# CheeseCake_1StAnn_SP.net
KiCad netlist of a schematic drawn in EasyEDA Pro
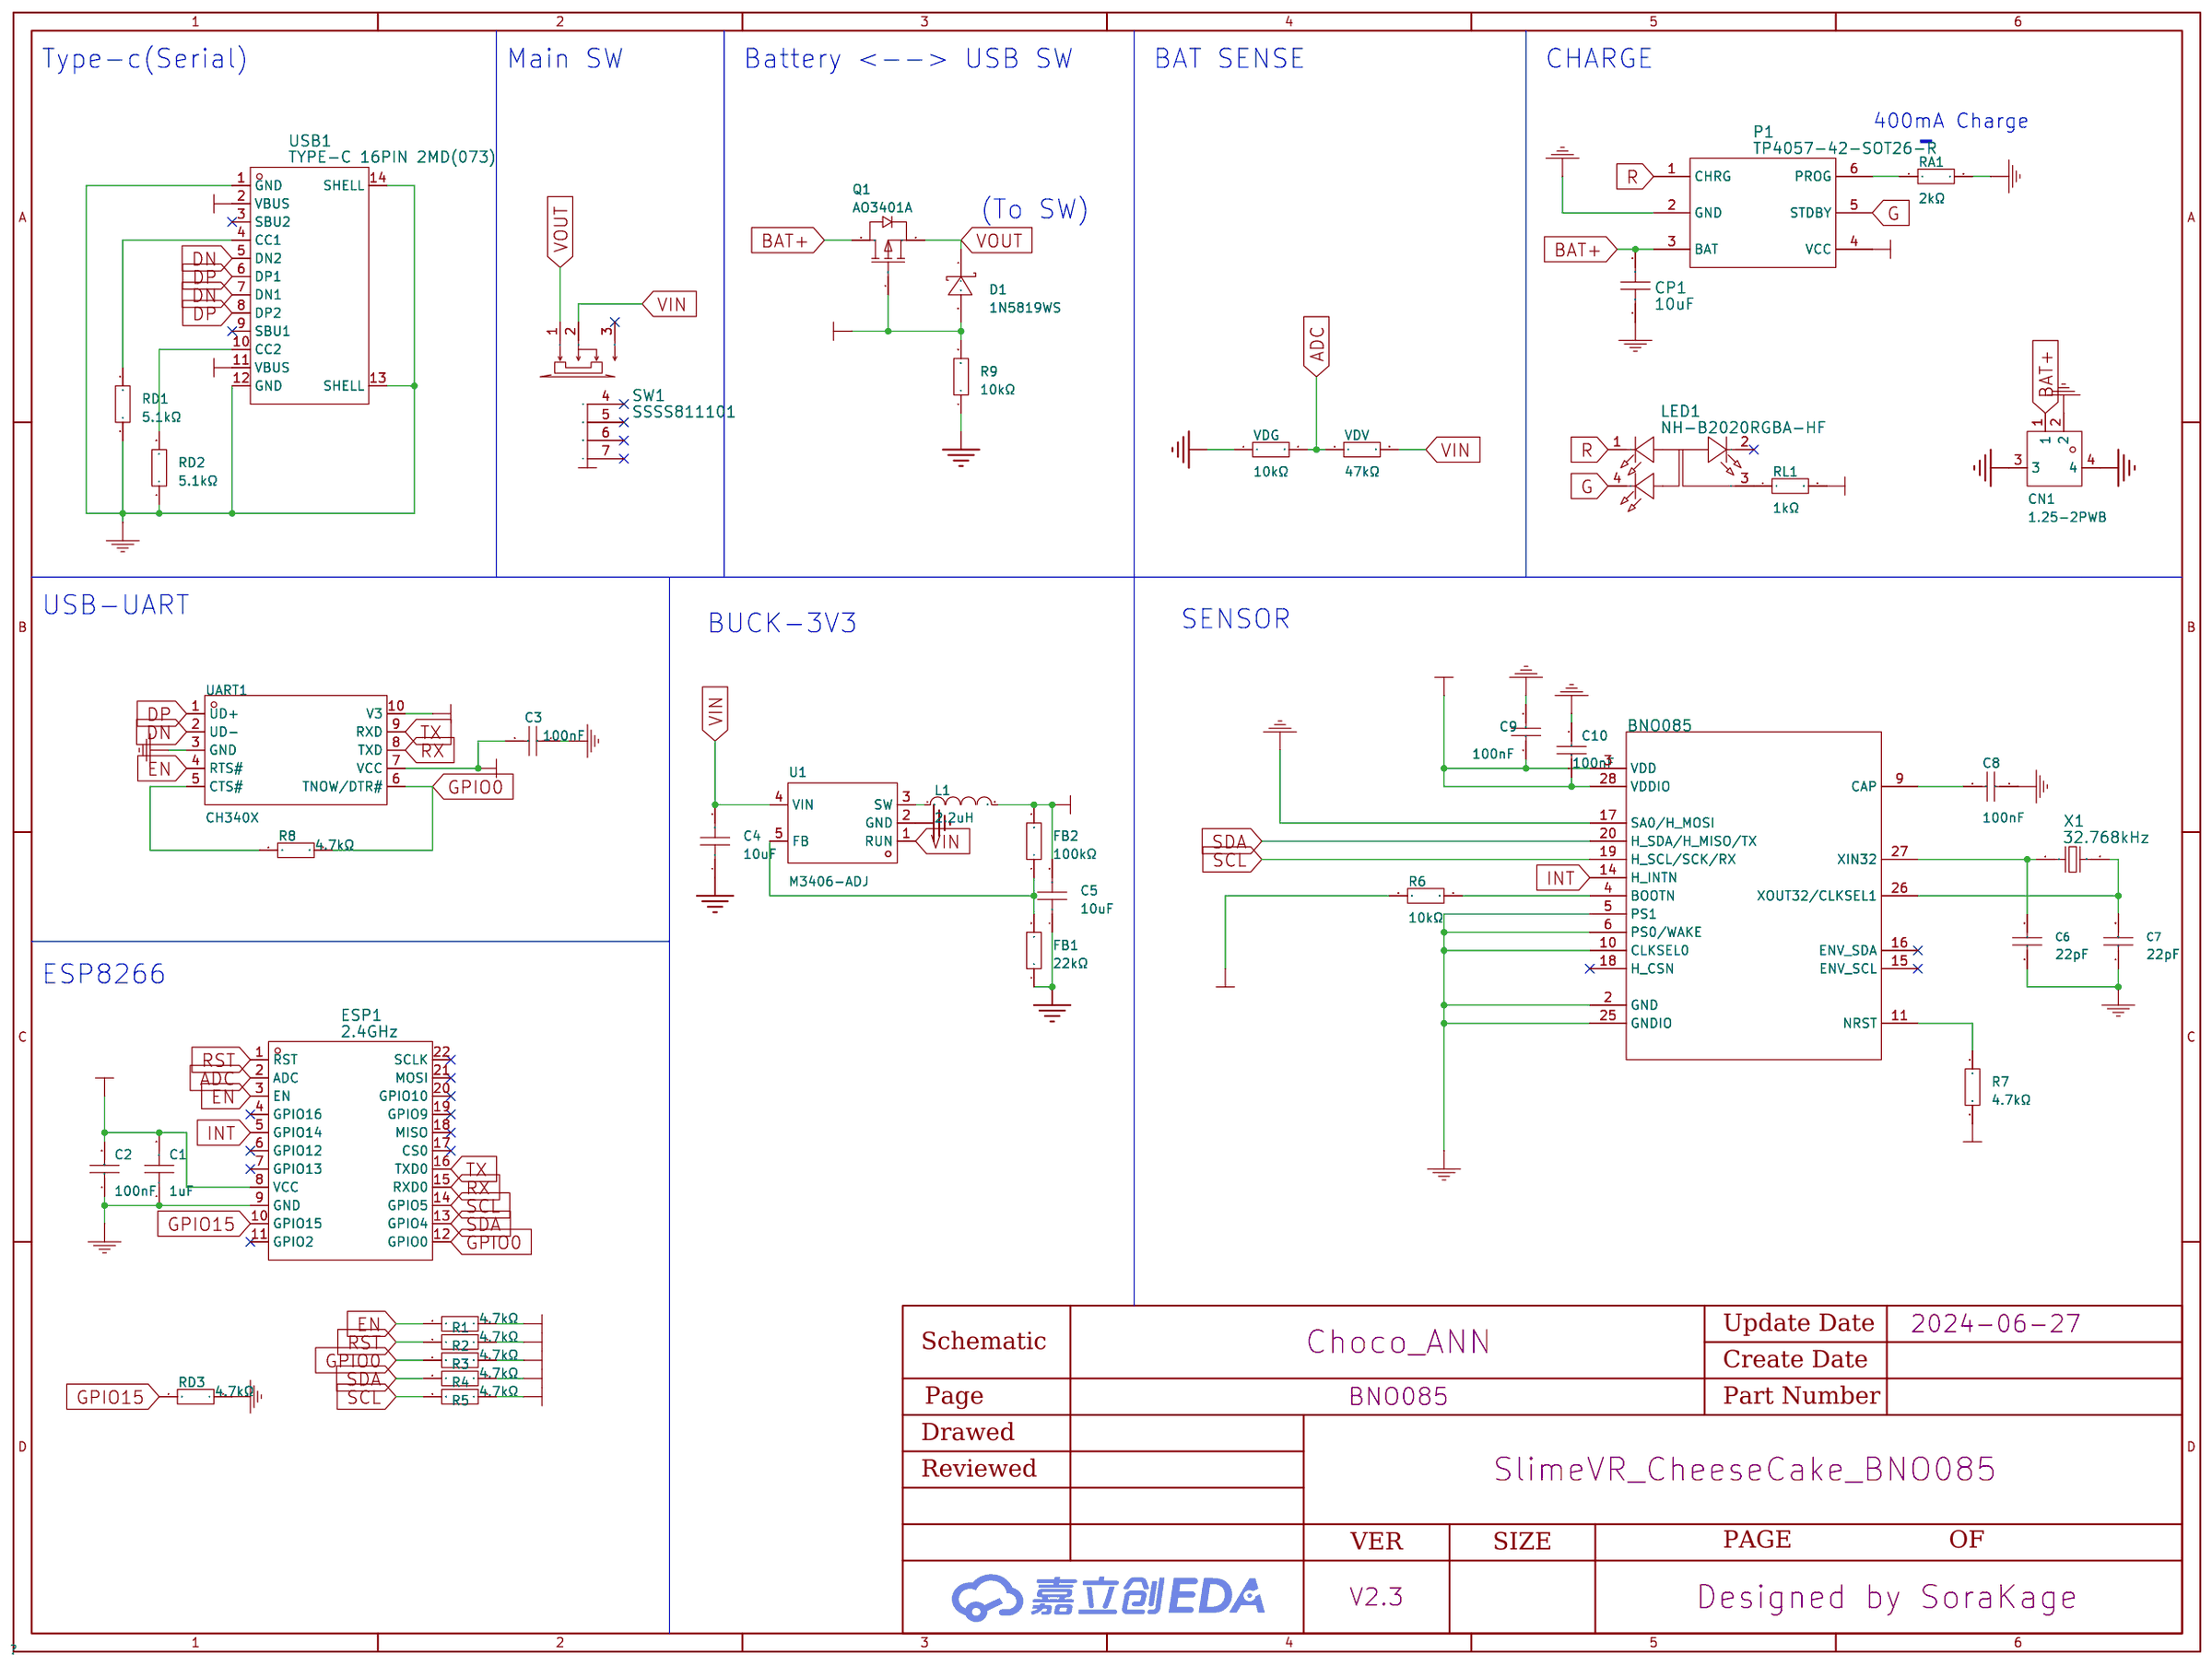
[diagram p0: schematic sheet]

(export (version "E")
  (design (tool "Eeschema 10.0.6"))
  (components
    (comp (ref "BNO085")
      (value "BNO080")
      (fields (field (name "Manufacturer Part") "BNO085") (field (name "Manufacturer") "Hillcrest"))
      (libsource (lib "easyedapro") (part "BNO080"))
    )
    (comp (ref "C1")
      (value "1uF")
      (footprint "easyedapro:C0402")
      (description "容值:1uF;精度:±10%;额定电压:25V;材质(温度系数):X5R;")
      (fields
        (field (name "Manufacturer Part") "CL05A105KA5NQNC")
        (field (name "Manufacturer") "SAMSUNG(三星)")
      )
      (libsource (lib "easyedapro") (part "CL05A105KA5NQNC"))
    )
    (comp (ref "C2")
      (value "100nF")
      (footprint "easyedapro:C0402")
      (description "容值:100nF;精度:±10%;额定电压:16V;材质(温度系数):X7R;")
      (fields
        (field (name "Manufacturer Part") "CL05B104KO5NNNC")
        (field (name "Manufacturer") "SAMSUNG(三星)")
      )
      (libsource (lib "easyedapro") (part "CL05B104KO5NNNC"))
    )
    (comp (ref "C3")
      (value "100nF")
      (footprint "easyedapro:C0402")
      (description "容值:100nF;精度:±10%;额定电压:16V;材质(温度系数):X7R;")
      (fields
        (field (name "Manufacturer Part") "CL05B104KO5NNNC")
        (field (name "Manufacturer") "SAMSUNG(三星)")
      )
      (libsource (lib "easyedapro") (part "CL05B104KO5NNNC"))
    )
    (comp (ref "C4")
      (value "10uF")
      (footprint "easyedapro:C0603")
      (description "容值:10uF;精度:±10%;额定电压:10V;材质(温度系数):X5R;")
      (fields
        (field (name "Manufacturer Part") "CL10A106KP8NNNC")
        (field (name "Manufacturer") "SAMSUNG(三星)")
      )
      (libsource (lib "easyedapro") (part "CL10A106KP8NNNC"))
    )
    (comp (ref "C5")
      (value "10uF")
      (footprint "easyedapro:C0603")
      (description "容值:10uF;精度:±10%;额定电压:10V;材质(温度系数):X5R;")
      (fields
        (field (name "Manufacturer Part") "CL10A106KP8NNNC")
        (field (name "Manufacturer") "SAMSUNG(三星)")
      )
      (libsource (lib "easyedapro") (part "CL10A106KP8NNNC"))
    )
    (comp (ref "C6")
      (value "22pF")
      (footprint "easyedapro:C0402")
      (description "容值:22pF;精度:±5%;额定电压:50V;材质(温度系数):C0G;")
      (fields (field (name "Manufacturer Part") "0402CG220J500NT") (field (name "Manufacturer") "FH(风华)"))
      (libsource (lib "easyedapro") (part "0402CG220J500NT"))
    )
    (comp (ref "C7")
      (value "22pF")
      (footprint "easyedapro:C0402")
      (description "容值:22pF;精度:±5%;额定电压:50V;材质(温度系数):C0G;")
      (fields (field (name "Manufacturer Part") "0402CG220J500NT") (field (name "Manufacturer") "FH(风华)"))
      (libsource (lib "easyedapro") (part "0402CG220J500NT"))
    )
    (comp (ref "C8")
      (value "100nF")
      (footprint "easyedapro:C0402")
      (description "容值:100nF;精度:±10%;额定电压:16V;材质(温度系数):X7R;")
      (fields
        (field (name "Manufacturer Part") "CL05B104KO5NNNC")
        (field (name "Manufacturer") "SAMSUNG(三星)")
      )
      (libsource (lib "easyedapro") (part "CL05B104KO5NNNC"))
    )
    (comp (ref "C9")
      (value "100nF")
      (footprint "easyedapro:C0402")
      (description "容值:100nF;精度:±10%;额定电压:16V;材质(温度系数):X7R;")
      (fields
        (field (name "Manufacturer Part") "CL05B104KO5NNNC")
        (field (name "Manufacturer") "SAMSUNG(三星)")
      )
      (libsource (lib "easyedapro") (part "CL05B104KO5NNNC"))
    )
    (comp (ref "C10")
      (value "100nF")
      (footprint "easyedapro:C0402")
      (description "容值:100nF;精度:±10%;额定电压:16V;材质(温度系数):X7R;")
      (fields
        (field (name "Manufacturer Part") "CL05B104KO5NNNC")
        (field (name "Manufacturer") "SAMSUNG(三星)")
      )
      (libsource (lib "easyedapro") (part "CL05B104KO5NNNC"))
    )
    (comp (ref "CN1")
      (value "1.25-2PWB")
      (footprint "easyedapro:CONN-SMD_2P-P1.25_DEALON_1.25-2PWB")
      (description "插针结构:1x2P;间距:1.25mm;安装方式:卧贴;参考系列:-;总PIN数:2P;排数:1;每排PIN数:2;行距:-;额定电流:-;工作温度范围:-40°C~+85°C;")
      (fields (field (name "Manufacturer") "DEALON(德艺隆)"))
      (libsource (lib "easyedapro") (part "1.25-2PWB"))
    )
    (comp (ref "CP1")
      (value "10uF")
      (footprint "easyedapro:C0603")
      (fields
        (field (name "Manufacturer Part") "CL10A106KP8NNNC")
        (field (name "Manufacturer") "SAMSUNG(三星)")
      )
      (libsource (lib "easyedapro") (part "10uF"))
    )
    (comp (ref "D1")
      (value "1N5819WS")
      (footprint "easyedapro:SOD-323_L1.8-W1.3-LS2.5-RD")
      (description "直流反向耐压(Vr):40V;平均整流电流(Io):1A;正向压降(Vf):600mV@1A;")
      (fields (field (name "Manufacturer") "Hottech(合科泰)"))
      (libsource (lib "easyedapro") (part "1N5819WS"))
    )
    (comp (ref "ESP1")
      (value "2.4GHz")
      (fields
        (field (name "Manufacturer Part") "ESP-12F(ESP8266MOD)")
        (field (name "Manufacturer") "Ai-Thinker(安信可)")
      )
      (libsource (lib "easyedapro") (part "ESP-12F(ESP8266MOD)"))
    )
    (comp (ref "FB1")
      (value "22kΩ")
      (footprint "easyedapro:R0402")
      (description "电阻类型:厚膜电阻;阻值:22kΩ;精度:±1%;功率:62.5mW;")
      (fields
        (field (name "Manufacturer Part") "0402WGF2202TCE")
        (field (name "Manufacturer") "UNI-ROYAL(厚声)")
      )
      (libsource (lib "easyedapro") (part "0402WGF2202TCE"))
    )
    (comp (ref "FB2")
      (value "100kΩ")
      (footprint "easyedapro:R0402")
      (description "电阻类型:厚膜电阻;阻值:100kΩ;精度:±1%;功率:62.5mW;")
      (fields
        (field (name "Manufacturer Part") "0402WGF1003TCE")
        (field (name "Manufacturer") "UNI-ROYAL(厚声)")
      )
      (libsource (lib "easyedapro") (part "0402WGF1003TCE"))
    )
    (comp (ref "L1")
      (value "2.2uH")
      (footprint "easyedapro:IND-SMD_L2.5-W2.0_YXMBL252010P")
      (description "类型:一体成型电感;电感值:2.2uH;精度:±20%;额定电流:2.1A;饱和电流(Isat):3A;")
      (fields (field (name "Manufacturer Part") "APH252010T2R2M") (field (name "Manufacturer") "APV(爱普微)"))
      (libsource (lib "easyedapro") (part "APH252010T2R2M"))
    )
    (comp (ref "LED1")
      (value "NH-B2020RGBA-HF")
      (footprint "easyedapro:LED-ARRAY-SMD_4P-L2.1-W2.1-TL_NH-B2020RGBA")
      (fields (field (name "Manufacturer") "国星光电"))
      (libsource (lib "easyedapro") (part "NH-B2020RGBA-HF"))
    )
    (comp (ref "P1")
      (value "TP4057-42-SOT26-R")
      (fields (field (name "Manufacturer") "TOPPOWER(南京拓微)"))
      (libsource (lib "easyedapro") (part "TP4057"))
    )
    (comp (ref "Q1")
      (value "AO3401A")
      (footprint "easyedapro:SOT-23_L2.9-W1.3-P1.90-LS2.4-BR")
      (description "类型:P沟道;漏源电压(Vdss):30V;连续漏极电流(Id):4A;功率(Pd):1.4W;导通电阻(RDS(on)@Vgs,Id):44mΩ@10V,4.3A;")
      (fields (field (name "Manufacturer") "AOS"))
      (libsource (lib "easyedapro") (part "AO3401A"))
    )
    (comp (ref "R1")
      (value "4.7kΩ")
      (footprint "easyedapro:R0402")
      (description "电阻类型:厚膜电阻;阻值:4.7kΩ;精度:±1%;功率:62.5mW;")
      (fields
        (field (name "Manufacturer Part") "0402WGF4701TCE")
        (field (name "Manufacturer") "UNI-ROYAL(厚声)")
      )
      (libsource (lib "easyedapro") (part "0402WGF4701TCE"))
    )
    (comp (ref "R2")
      (value "4.7kΩ")
      (footprint "easyedapro:R0402")
      (description "电阻类型:厚膜电阻;阻值:4.7kΩ;精度:±1%;功率:62.5mW;")
      (fields
        (field (name "Manufacturer Part") "0402WGF4701TCE")
        (field (name "Manufacturer") "UNI-ROYAL(厚声)")
      )
      (libsource (lib "easyedapro") (part "0402WGF4701TCE"))
    )
    (comp (ref "R3")
      (value "4.7kΩ")
      (footprint "easyedapro:R0402")
      (description "电阻类型:厚膜电阻;阻值:4.7kΩ;精度:±1%;功率:62.5mW;")
      (fields
        (field (name "Manufacturer Part") "0402WGF4701TCE")
        (field (name "Manufacturer") "UNI-ROYAL(厚声)")
      )
      (libsource (lib "easyedapro") (part "0402WGF4701TCE"))
    )
    (comp (ref "R4")
      (value "4.7kΩ")
      (footprint "easyedapro:R0402")
      (description "电阻类型:厚膜电阻;阻值:4.7kΩ;精度:±1%;功率:62.5mW;")
      (fields
        (field (name "Manufacturer Part") "0402WGF4701TCE")
        (field (name "Manufacturer") "UNI-ROYAL(厚声)")
      )
      (libsource (lib "easyedapro") (part "0402WGF4701TCE"))
    )
    (comp (ref "R5")
      (value "4.7kΩ")
      (footprint "easyedapro:R0402")
      (description "电阻类型:厚膜电阻;阻值:4.7kΩ;精度:±1%;功率:62.5mW;")
      (fields
        (field (name "Manufacturer Part") "0402WGF4701TCE")
        (field (name "Manufacturer") "UNI-ROYAL(厚声)")
      )
      (libsource (lib "easyedapro") (part "0402WGF4701TCE"))
    )
    (comp (ref "R6")
      (value "10kΩ")
      (footprint "easyedapro:R0402")
      (description "电阻类型:厚膜电阻;阻值:10kΩ;精度:±1%;功率:62.5mW;")
      (fields
        (field (name "Manufacturer Part") "0402WGF1002TCE")
        (field (name "Manufacturer") "UNI-ROYAL(厚声)")
      )
      (libsource (lib "easyedapro") (part "0402WGF1002TCE"))
    )
    (comp (ref "R7")
      (value "4.7kΩ")
      (footprint "easyedapro:R0402")
      (description "电阻类型:厚膜电阻;阻值:4.7kΩ;精度:±1%;功率:62.5mW;")
      (fields
        (field (name "Manufacturer Part") "0402WGF4701TCE")
        (field (name "Manufacturer") "UNI-ROYAL(厚声)")
      )
      (libsource (lib "easyedapro") (part "0402WGF4701TCE"))
    )
    (comp (ref "R8")
      (value "4.7kΩ")
      (footprint "easyedapro:R0402")
      (description "电阻类型:厚膜电阻;阻值:4.7kΩ;精度:±1%;功率:62.5mW;")
      (fields
        (field (name "Manufacturer Part") "0402WGF4701TCE")
        (field (name "Manufacturer") "UNI-ROYAL(厚声)")
      )
      (libsource (lib "easyedapro") (part "0402WGF4701TCE"))
    )
    (comp (ref "R9")
      (value "10kΩ")
      (footprint "easyedapro:R0402")
      (description "电阻类型:厚膜电阻;阻值:10kΩ;精度:±1%;功率:62.5mW;")
      (fields
        (field (name "Manufacturer Part") "0402WGF1002TCE")
        (field (name "Manufacturer") "UNI-ROYAL(厚声)")
      )
      (libsource (lib "easyedapro") (part "0402WGF1002TCE"))
    )
    (comp (ref "RA1")
      (value "2kΩ")
      (footprint "easyedapro:R0402")
      (description "电阻类型:厚膜电阻;阻值:2kΩ;精度:±1%;功率:62.5mW;")
      (fields
        (field (name "Manufacturer Part") "0402WGF2001TCE")
        (field (name "Manufacturer") "UNI-ROYAL(厚声)")
      )
      (libsource (lib "easyedapro") (part "0402WGF2001TCE"))
    )
    (comp (ref "RD1")
      (value "5.1kΩ")
      (footprint "easyedapro:R0402")
      (description "电阻类型:厚膜电阻;阻值:5.1kΩ;精度:±1%;功率:62.5mW;")
      (fields
        (field (name "Manufacturer Part") "0402WGF5101TCE")
        (field (name "Manufacturer") "UNI-ROYAL(厚声)")
      )
      (libsource (lib "easyedapro") (part "0402WGF5101TCE"))
    )
    (comp (ref "RD2")
      (value "5.1kΩ")
      (footprint "easyedapro:R0402")
      (description "电阻类型:厚膜电阻;阻值:5.1kΩ;精度:±1%;功率:62.5mW;")
      (fields
        (field (name "Manufacturer Part") "0402WGF5101TCE")
        (field (name "Manufacturer") "UNI-ROYAL(厚声)")
      )
      (libsource (lib "easyedapro") (part "0402WGF5101TCE"))
    )
    (comp (ref "RD3")
      (value "4.7kΩ")
      (footprint "easyedapro:R0402")
      (description "电阻类型:厚膜电阻;阻值:4.7kΩ;精度:±1%;功率:62.5mW;")
      (fields
        (field (name "Manufacturer Part") "0402WGF4701TCE")
        (field (name "Manufacturer") "UNI-ROYAL(厚声)")
      )
      (libsource (lib "easyedapro") (part "0402WGF4701TCE"))
    )
    (comp (ref "RL1")
      (value "1kΩ")
      (footprint "easyedapro:R0402")
      (description "电阻类型:厚膜电阻;阻值:1kΩ;精度:±1%;功率:62.5mW;")
      (fields
        (field (name "Manufacturer Part") "0402WGF1001TCE")
        (field (name "Manufacturer") "UNI-ROYAL(厚声)")
      )
      (libsource (lib "easyedapro") (part "0402WGF1001TCE"))
    )
    (comp (ref "SW1")
      (value "SSSS811101")
      (footprint "easyedapro:SW-SMD_SSSS811101")
      (fields (field (name "Manufacturer") "ALPSALPINE(阿尔卑斯阿尔派)"))
      (libsource (lib "easyedapro") (part "SSSS811101"))
    )
    (comp (ref "U1")
      (value "M3406-ADJ")
      (footprint "easyedapro:SOT-23-5_L3.0-W1.7-P0.95-LS2.8-BR")
      (description "功能类型:降压型;同步整流:-;输出通道数:-;拓扑结构:-;输入电压:-;输出电流(最大值):-;开关频率:-;")
      (fields (field (name "Manufacturer") "西安航天民芯"))
      (libsource (lib "easyedapro") (part "M3406"))
    )
    (comp (ref "UART1")
      (value "CH340X")
      (footprint "easyedapro:MSOP-10_L3.0-W3.0-P0.50-LS5.0-BL")
      (fields (field (name "Manufacturer") "WCH(南京沁恒)"))
      (libsource (lib "easyedapro") (part "CH340X"))
    )
    (comp (ref "USB1")
      (value "TYPE-C 16PIN 2MD(073)")
      (footprint "easyedapro:USB-C-SMD_TYPE-C-6PIN-2MD-073")
      (fields (field (name "Manufacturer") "SHOU HAN(首韩)"))
      (libsource (lib "easyedapro") (part "TYPE-C 16PIN 2MD(073)"))
    )
    (comp (ref "VDG")
      (value "10kΩ")
      (footprint "easyedapro:R0402")
      (description "电阻类型:厚膜电阻;阻值:10kΩ;精度:±1%;功率:62.5mW;")
      (fields
        (field (name "Manufacturer Part") "0402WGF1002TCE")
        (field (name "Manufacturer") "UNI-ROYAL(厚声)")
      )
      (libsource (lib "easyedapro") (part "0402WGF1002TCE"))
    )
    (comp (ref "VDV")
      (value "47kΩ")
      (footprint "easyedapro:R0402")
      (description "电阻类型:厚膜电阻;阻值:47kΩ;精度:±1%;功率:62.5mW;")
      (fields
        (field (name "Manufacturer Part") "0402WGF4702TCE")
        (field (name "Manufacturer") "UNI-ROYAL(厚声)")
      )
      (libsource (lib "easyedapro") (part "0402WGF4702TCE"))
    )
    (comp (ref "X1")
      (value "32.768kHz")
      (fields (field (name "Manufacturer Part") "Q13FC1350000400") (field (name "Manufacturer") "EPSON(爱普生)"))
      (libsource (lib "easyedapro") (part "32.768kHz"))
    )
  )
  (nets
    (net (code "1") (name "+5V") (class "Default")
      (node (ref "D1") (pin "2") (pinfunction "A_2") (pintype "unspecified"))
      (node (ref "P1") (pin "4") (pinfunction "VCC_4") (pintype "input"))
      (node (ref "Q1") (pin "1") (pinfunction "G_1") (pintype "input"))
      (node (ref "R9") (pin "2") (pinfunction "2_2") (pintype "input"))
      (node (ref "RL1") (pin "2") (pinfunction "2_2") (pintype "input"))
      (node (ref "USB1") (pin "11") (pinfunction "VBUS_11") (pintype "input"))
      (node (ref "USB1") (pin "2") (pinfunction "VBUS_2") (pintype "input"))
    )
    (net (code "2") (name "3V3") (class "Default")
      (node (ref "BNO085") (pin "28") (pinfunction "VDDIO_28") (pintype "input"))
      (node (ref "BNO085") (pin "3") (pinfunction "VDD_3") (pintype "input"))
      (node (ref "C1") (pin "2") (pinfunction "2_2") (pintype "unspecified"))
      (node (ref "C10") (pin "2") (pinfunction "2_2") (pintype "input"))
      (node (ref "C2") (pin "2") (pinfunction "2_2") (pintype "input"))
      (node (ref "C3") (pin "2") (pinfunction "2_2") (pintype "input"))
      (node (ref "C5") (pin "2") (pinfunction "2_2") (pintype "unspecified"))
      (node (ref "C9") (pin "2") (pinfunction "2_2") (pintype "input"))
      (node (ref "ESP1") (pin "8") (pinfunction "VCC_8") (pintype "input"))
      (node (ref "FB2") (pin "2") (pinfunction "2_2") (pintype "input"))
      (node (ref "L1") (pin "2") (pinfunction "2_2") (pintype "unspecified"))
      (node (ref "R1") (pin "1") (pinfunction "1_1") (pintype "input"))
      (node (ref "R2") (pin "1") (pinfunction "1_1") (pintype "input"))
      (node (ref "R3") (pin "1") (pinfunction "1_1") (pintype "input"))
      (node (ref "R4") (pin "1") (pinfunction "1_1") (pintype "input"))
      (node (ref "R5") (pin "1") (pinfunction "1_1") (pintype "input"))
      (node (ref "R6") (pin "1") (pinfunction "1_1") (pintype "input"))
      (node (ref "R7") (pin "2") (pinfunction "2_2") (pintype "input"))
      (node (ref "UART1") (pin "10") (pinfunction "V3_10") (pintype "unspecified"))
      (node (ref "UART1") (pin "7") (pinfunction "VCC_7") (pintype "unspecified"))
    )
    (net (code "3") (name "ADC") (class "Default")
      (node (ref "ESP1") (pin "2") (pinfunction "ADC_2") (pintype "input"))
      (node (ref "VDG") (pin "2") (pinfunction "2_2") (pintype "input"))
      (node (ref "VDV") (pin "1") (pinfunction "1_1") (pintype "input"))
    )
    (net (code "4") (name "BAT+") (class "Default")
      (node (ref "CN1") (pin "1") (pinfunction "1_1") (pintype "unspecified"))
      (node (ref "CP1") (pin "2") (pinfunction "2_2") (pintype "input"))
      (node (ref "P1") (pin "3") (pinfunction "BAT_3") (pintype "input"))
      (node (ref "Q1") (pin "3") (pinfunction "D_3") (pintype "input"))
    )
    (net (code "5") (name "DN") (class "Default")
      (node (ref "UART1") (pin "2") (pinfunction "UD-_2") (pintype "unspecified"))
      (node (ref "USB1") (pin "5") (pinfunction "DN2_5") (pintype "input"))
      (node (ref "USB1") (pin "7") (pinfunction "DN1_7") (pintype "input"))
    )
    (net (code "6") (name "DP") (class "Default")
      (node (ref "UART1") (pin "1") (pinfunction "UD+_1") (pintype "unspecified"))
      (node (ref "USB1") (pin "6") (pinfunction "DP1_6") (pintype "input"))
      (node (ref "USB1") (pin "8") (pinfunction "DP2_8") (pintype "input"))
    )
    (net (code "7") (name "EN") (class "Default")
      (node (ref "ESP1") (pin "3") (pinfunction "EN_3") (pintype "input"))
      (node (ref "R1") (pin "2") (pinfunction "2_2") (pintype "input"))
      (node (ref "UART1") (pin "4") (pinfunction "RTS#_4") (pintype "unspecified"))
    )
    (net (code "8") (name "G") (class "Default")
      (node (ref "LED1") (pin "4") (pinfunction "-_4") (pintype "input"))
      (node (ref "P1") (pin "5") (pinfunction "STDBY_5") (pintype "input"))
    )
    (net (code "9") (name "GND") (class "Default")
      (node (ref "BNO085") (pin "10") (pinfunction "CLKSEL0_10") (pintype "input"))
      (node (ref "BNO085") (pin "17") (pinfunction "SA0/H_MOSI_17") (pintype "input"))
      (node (ref "BNO085") (pin "2") (pinfunction "GND_2") (pintype "input"))
      (node (ref "BNO085") (pin "25") (pinfunction "GNDIO_25") (pintype "input"))
      (node (ref "BNO085") (pin "5") (pinfunction "PS1_5") (pintype "input"))
      (node (ref "BNO085") (pin "6") (pinfunction "PS0/WAKE_6") (pintype "input"))
      (node (ref "C1") (pin "1") (pinfunction "1_1") (pintype "unspecified"))
      (node (ref "C10") (pin "1") (pinfunction "1_1") (pintype "input"))
      (node (ref "C2") (pin "1") (pinfunction "1_1") (pintype "input"))
      (node (ref "C3") (pin "1") (pinfunction "1_1") (pintype "input"))
      (node (ref "C4") (pin "1") (pinfunction "1_1") (pintype "unspecified"))
      (node (ref "C5") (pin "1") (pinfunction "1_1") (pintype "unspecified"))
      (node (ref "C6") (pin "1") (pinfunction "1_1") (pintype "input"))
      (node (ref "C7") (pin "1") (pinfunction "1_1") (pintype "input"))
      (node (ref "C8") (pin "2") (pinfunction "2_2") (pintype "input"))
      (node (ref "C9") (pin "1") (pinfunction "1_1") (pintype "input"))
      (node (ref "CN1") (pin "2") (pinfunction "2_2") (pintype "unspecified"))
      (node (ref "CN1") (pin "3") (pinfunction "3_3") (pintype "unspecified"))
      (node (ref "CN1") (pin "4") (pinfunction "4_4") (pintype "unspecified"))
      (node (ref "CP1") (pin "1") (pinfunction "1_1") (pintype "input"))
      (node (ref "ESP1") (pin "9") (pinfunction "GND_9") (pintype "input"))
      (node (ref "FB1") (pin "1") (pinfunction "1_1") (pintype "input"))
      (node (ref "P1") (pin "2") (pinfunction "GND_2") (pintype "input"))
      (node (ref "R9") (pin "1") (pinfunction "1_1") (pintype "input"))
      (node (ref "RA1") (pin "2") (pinfunction "2_2") (pintype "input"))
      (node (ref "RD1") (pin "1") (pinfunction "1_1") (pintype "input"))
      (node (ref "RD2") (pin "1") (pinfunction "1_1") (pintype "input"))
      (node (ref "RD3") (pin "1") (pinfunction "1_1") (pintype "input"))
      (node (ref "U1") (pin "2") (pinfunction "GND_2") (pintype "input"))
      (node (ref "UART1") (pin "3") (pinfunction "GND_3") (pintype "unspecified"))
      (node (ref "USB1") (pin "1") (pinfunction "GND_1") (pintype "input"))
      (node (ref "USB1") (pin "12") (pinfunction "GND_12") (pintype "input"))
      (node (ref "USB1") (pin "13") (pinfunction "SHELL_13") (pintype "input"))
      (node (ref "USB1") (pin "14") (pinfunction "SHELL_14") (pintype "input"))
      (node (ref "VDG") (pin "1") (pinfunction "1_1") (pintype "input"))
    )
    (net (code "10") (name "GPIO0") (class "Default")
      (node (ref "ESP1") (pin "12") (pinfunction "GPIO0_12") (pintype "input"))
      (node (ref "R3") (pin "2") (pinfunction "2_2") (pintype "input"))
      (node (ref "R8") (pin "1") (pinfunction "1_1") (pintype "input"))
      (node (ref "UART1") (pin "6") (pinfunction "TNOW/DTR#_6") (pintype "unspecified"))
    )
    (net (code "11") (name "GPIO15") (class "Default")
      (node (ref "ESP1") (pin "10") (pinfunction "GPIO15_10") (pintype "input"))
      (node (ref "RD3") (pin "2") (pinfunction "2_2") (pintype "input"))
    )
    (net (code "12") (name "INT") (class "Default")
      (node (ref "BNO085") (pin "14") (pinfunction "H_INTN_14") (pintype "input"))
      (node (ref "ESP1") (pin "5") (pinfunction "GPIO14_5") (pintype "input"))
    )
    (net (code "13") (name "Net-(BNO085-BOOTN)") (class "Default")
      (node (ref "BNO085") (pin "4") (pinfunction "BOOTN_4") (pintype "input"))
      (node (ref "R6") (pin "2") (pinfunction "2_2") (pintype "input"))
    )
    (net (code "14") (name "Net-(BNO085-CAP)") (class "Default")
      (node (ref "BNO085") (pin "9") (pinfunction "CAP_9") (pintype "input"))
      (node (ref "C8") (pin "1") (pinfunction "1_1") (pintype "input"))
    )
    (net (code "15") (name "Net-(BNO085-NRST)") (class "Default")
      (node (ref "BNO085") (pin "11") (pinfunction "NRST_11") (pintype "input"))
      (node (ref "R7") (pin "1") (pinfunction "1_1") (pintype "input"))
    )
    (net (code "16") (name "Net-(BNO085-XIN32)") (class "Default")
      (node (ref "BNO085") (pin "27") (pinfunction "XIN32_27") (pintype "input"))
      (node (ref "C6") (pin "2") (pinfunction "2_2") (pintype "input"))
      (node (ref "X1") (pin "1") (pinfunction "1_1") (pintype "input"))
    )
    (net (code "17") (name "Net-(BNO085-XOUT32{slash}CLKSEL1)") (class "Default")
      (node (ref "BNO085") (pin "26") (pinfunction "XOUT32/CLKSEL1_26") (pintype "input"))
      (node (ref "C7") (pin "2") (pinfunction "2_2") (pintype "input"))
      (node (ref "X1") (pin "2") (pinfunction "2_2") (pintype "input"))
    )
    (net (code "18") (name "Net-(LED1-+)") (class "Default")
      (node (ref "LED1") (pin "3") (pinfunction "+_3") (pintype "input"))
      (node (ref "RL1") (pin "1") (pinfunction "1_1") (pintype "input"))
    )
    (net (code "19") (name "Net-(P1-PROG)") (class "Default")
      (node (ref "P1") (pin "6") (pinfunction "PROG_6") (pintype "input"))
      (node (ref "RA1") (pin "1") (pinfunction "1_1") (pintype "input"))
    )
    (net (code "20") (name "Net-(U1-FB)") (class "Default")
      (node (ref "FB1") (pin "2") (pinfunction "2_2") (pintype "input"))
      (node (ref "FB2") (pin "1") (pinfunction "1_1") (pintype "input"))
      (node (ref "U1") (pin "5") (pinfunction "FB_5") (pintype "input"))
    )
    (net (code "21") (name "Net-(U1-SW)") (class "Default")
      (node (ref "L1") (pin "1") (pinfunction "1_1") (pintype "unspecified"))
      (node (ref "U1") (pin "3") (pinfunction "SW_3") (pintype "input"))
    )
    (net (code "22") (name "Net-(UART1-CTS#)") (class "Default")
      (node (ref "R8") (pin "2") (pinfunction "2_2") (pintype "input"))
      (node (ref "UART1") (pin "5") (pinfunction "CTS#_5") (pintype "unspecified"))
    )
    (net (code "23") (name "Net-(USB1-CC1)") (class "Default")
      (node (ref "RD1") (pin "2") (pinfunction "2_2") (pintype "input"))
      (node (ref "USB1") (pin "4") (pinfunction "CC1_4") (pintype "input"))
    )
    (net (code "24") (name "Net-(USB1-CC2)") (class "Default")
      (node (ref "RD2") (pin "2") (pinfunction "2_2") (pintype "input"))
      (node (ref "USB1") (pin "10") (pinfunction "CC2_10") (pintype "input"))
    )
    (net (code "25") (name "R") (class "Default")
      (node (ref "LED1") (pin "1") (pinfunction "-_1") (pintype "input"))
      (node (ref "P1") (pin "1") (pinfunction "CHRG_1") (pintype "input"))
    )
    (net (code "26") (name "RST") (class "Default")
      (node (ref "ESP1") (pin "1") (pinfunction "RST_1") (pintype "input"))
      (node (ref "R2") (pin "2") (pinfunction "2_2") (pintype "input"))
    )
    (net (code "27") (name "RX") (class "Default")
      (node (ref "ESP1") (pin "15") (pinfunction "RXD0_15") (pintype "input"))
      (node (ref "UART1") (pin "8") (pinfunction "TXD_8") (pintype "unspecified"))
    )
    (net (code "28") (name "SCL") (class "Default")
      (node (ref "BNO085") (pin "19") (pinfunction "H_SCL/SCK/RX_19") (pintype "input"))
      (node (ref "ESP1") (pin "14") (pinfunction "GPIO5_14") (pintype "input"))
      (node (ref "R5") (pin "2") (pinfunction "2_2") (pintype "input"))
    )
    (net (code "29") (name "SDA") (class "Default")
      (node (ref "BNO085") (pin "20") (pinfunction "H_SDA/H_MISO/TX_20") (pintype "input"))
      (node (ref "ESP1") (pin "13") (pinfunction "GPIO4_13") (pintype "input"))
      (node (ref "R4") (pin "2") (pinfunction "2_2") (pintype "input"))
    )
    (net (code "30") (name "TX") (class "Default")
      (node (ref "ESP1") (pin "16") (pinfunction "TXD0_16") (pintype "input"))
      (node (ref "UART1") (pin "9") (pinfunction "RXD_9") (pintype "unspecified"))
    )
    (net (code "31") (name "VIN") (class "Default")
      (node (ref "C4") (pin "2") (pinfunction "2_2") (pintype "unspecified"))
      (node (ref "SW1") (pin "2") (pinfunction "2_2") (pintype "input"))
      (node (ref "U1") (pin "1") (pinfunction "RUN_1") (pintype "input"))
      (node (ref "U1") (pin "4") (pinfunction "VIN_4") (pintype "input"))
      (node (ref "VDV") (pin "2") (pinfunction "2_2") (pintype "input"))
    )
    (net (code "32") (name "VOUT") (class "Default")
      (node (ref "D1") (pin "1") (pinfunction "K_1") (pintype "unspecified"))
      (node (ref "Q1") (pin "2") (pinfunction "S_2") (pintype "input"))
      (node (ref "SW1") (pin "1") (pinfunction "1_1") (pintype "input"))
    )
    (net (code "33") (name "unconnected-(BNO085-ENV_SCL-Pad15)") (class "Default")
      (node (ref "BNO085") (pin "15") (pinfunction "ENV_SCL_15") (pintype "input+no_connect"))
    )
    (net (code "34") (name "unconnected-(BNO085-ENV_SDA-Pad16)") (class "Default")
      (node (ref "BNO085") (pin "16") (pinfunction "ENV_SDA_16") (pintype "input+no_connect"))
    )
    (net (code "35") (name "unconnected-(BNO085-H_CSN-Pad18)") (class "Default")
      (node (ref "BNO085") (pin "18") (pinfunction "H_CSN_18") (pintype "input+no_connect"))
    )
    (net (code "36") (name "unconnected-(ESP1-CS0-Pad17)") (class "Default")
      (node (ref "ESP1") (pin "17") (pinfunction "CS0_17") (pintype "input+no_connect"))
    )
    (net (code "37") (name "unconnected-(ESP1-GPIO2-Pad11)") (class "Default")
      (node (ref "ESP1") (pin "11") (pinfunction "GPIO2_11") (pintype "input+no_connect"))
    )
    (net (code "38") (name "unconnected-(ESP1-GPIO9-Pad19)") (class "Default")
      (node (ref "ESP1") (pin "19") (pinfunction "GPIO9_19") (pintype "input+no_connect"))
    )
    (net (code "39") (name "unconnected-(ESP1-GPIO10-Pad20)") (class "Default")
      (node (ref "ESP1") (pin "20") (pinfunction "GPIO10_20") (pintype "input+no_connect"))
    )
    (net (code "40") (name "unconnected-(ESP1-GPIO12-Pad6)") (class "Default")
      (node (ref "ESP1") (pin "6") (pinfunction "GPIO12_6") (pintype "input+no_connect"))
    )
    (net (code "41") (name "unconnected-(ESP1-GPIO13-Pad7)") (class "Default")
      (node (ref "ESP1") (pin "7") (pinfunction "GPIO13_7") (pintype "input+no_connect"))
    )
    (net (code "42") (name "unconnected-(ESP1-GPIO16-Pad4)") (class "Default")
      (node (ref "ESP1") (pin "4") (pinfunction "GPIO16_4") (pintype "input+no_connect"))
    )
    (net (code "43") (name "unconnected-(ESP1-MISO-Pad18)") (class "Default")
      (node (ref "ESP1") (pin "18") (pinfunction "MISO_18") (pintype "input+no_connect"))
    )
    (net (code "44") (name "unconnected-(ESP1-MOSI-Pad21)") (class "Default")
      (node (ref "ESP1") (pin "21") (pinfunction "MOSI_21") (pintype "input+no_connect"))
    )
    (net (code "45") (name "unconnected-(ESP1-SCLK-Pad22)") (class "Default")
      (node (ref "ESP1") (pin "22") (pinfunction "SCLK_22") (pintype "input+no_connect"))
    )
    (net (code "46") (name "unconnected-(LED1---Pad2)") (class "Default")
      (node (ref "LED1") (pin "2") (pinfunction "-_2") (pintype "input+no_connect"))
    )
    (net (code "47") (name "unconnected-(SW1-Pad3)") (class "Default")
      (node (ref "SW1") (pin "3") (pinfunction "3_3") (pintype "input+no_connect"))
    )
    (net (code "48") (name "unconnected-(SW1-Pad4)") (class "Default")
      (node (ref "SW1") (pin "4") (pinfunction "4_4") (pintype "input+no_connect"))
    )
    (net (code "49") (name "unconnected-(SW1-Pad5)") (class "Default")
      (node (ref "SW1") (pin "5") (pinfunction "5_5") (pintype "input+no_connect"))
    )
    (net (code "50") (name "unconnected-(SW1-Pad6)") (class "Default")
      (node (ref "SW1") (pin "6") (pinfunction "6_6") (pintype "input+no_connect"))
    )
    (net (code "51") (name "unconnected-(SW1-Pad7)") (class "Default")
      (node (ref "SW1") (pin "7") (pinfunction "7_7") (pintype "input+no_connect"))
    )
    (net (code "52") (name "unconnected-(USB1-SBU1-Pad9)") (class "Default")
      (node (ref "USB1") (pin "9") (pinfunction "SBU1_9") (pintype "input+no_connect"))
    )
    (net (code "53") (name "unconnected-(USB1-SBU2-Pad3)") (class "Default")
      (node (ref "USB1") (pin "3") (pinfunction "SBU2_3") (pintype "input+no_connect"))
    )
  )
)
